# v1_0.net
KiCad netlist of a schematic drawn in Altium Designer
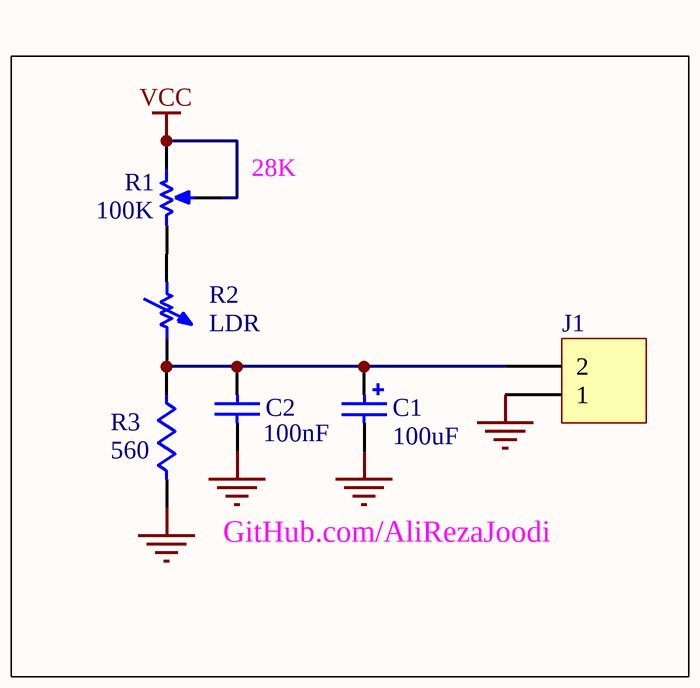
[diagram p0: v1.0.SchDoc]

(export (version "E")
  (design (tool "Eeschema 10.0.6"))
  (components
    (comp (ref "C1")
      (value "100uF")
      (footprint "CAPPR2.5-6.3x5")
      (description "Polarized Capacitor (Radial)")
      (fields
        (field (name "MANUFACTURER") "Generic Components")
        (field (name "Comment") "Cap Pol1")
        (field (name "PUBLISHER") "Altium Limited")
      )
      (libsource (lib "Miscellaneous Devices") (part "Cap Pol1"))
    )
    (comp (ref "C2")
      (value "100nF")
      (footprint "CAPNTO2.54-3.05x1.78A")
      (description "Capacitor")
      (fields
        (field (name "MANUFACTURER") "Generic Components")
        (field (name "Comment") "Cap")
        (field (name "PUBLISHER") "Altium Limited")
      )
      (libsource (lib "Miscellaneous Devices") (part "Cap"))
    )
    (comp (ref "J1")
      (value "Header")
      (footprint "Fonics_2PIN_1")
      (description "Header, 2-Pin")
      (fields (field (name "PUBLISHER") "Altium Limited"))
      (libsource (lib "Miscellaneous Connectors") (part "Header 2"))
    )
    (comp (ref "R1")
      (value "100K")
      (footprint "VR4_")
      (description "Potentiometer")
      (fields
        (field (name "MANUFACTURER") "Generic Components")
        (field (name "Comment") "R15")
        (field (name "PUBLISHER") "Altium Limited")
      )
      (libsource (lib "my Libraries") (part "RPot1"))
    )
    (comp (ref "R2")
      (value "LDR")
      (footprint "Fonics_2PIN_1")
      (description "Variable Resistor")
      (fields
        (field (name "MANUFACTURER") "Generic Components")
        (field (name "Comment") "Res Adj1")
        (field (name "PUBLISHER") "Altium Limited")
      )
      (libsource (lib "Miscellaneous Devices") (part "Res Adj1"))
    )
    (comp (ref "R3")
      (value "560")
      (footprint "AXIAL-0.4")
      (description "Resistor")
      (fields
        (field (name "MANUFACTURER") "Generic Components")
        (field (name "Comment") "Res1")
        (field (name "PUBLISHER") "Altium Limited")
      )
      (libsource (lib "Miscellaneous Devices") (part "Res1"))
    )
  )
  (nets
    (net (code "1") (name "GND") (class "Default")
      (node (ref "C1") (pin "2") (pinfunction "2_2") (pintype "passive"))
      (node (ref "C2") (pin "1") (pinfunction "1_1") (pintype "passive"))
      (node (ref "J1") (pin "1") (pinfunction "1_1") (pintype "passive"))
      (node (ref "R3") (pin "2") (pinfunction "2_2") (pintype "passive"))
    )
    (net (code "2") (name "Net-(C1-Pad1)") (class "Default")
      (node (ref "C1") (pin "1") (pinfunction "1_1") (pintype "passive"))
      (node (ref "C2") (pin "2") (pinfunction "2_2") (pintype "passive"))
      (node (ref "J1") (pin "2") (pinfunction "2_2") (pintype "passive"))
      (node (ref "R2") (pin "2") (pinfunction "2_2") (pintype "passive"))
      (node (ref "R3") (pin "1") (pinfunction "1_1") (pintype "passive"))
    )
    (net (code "3") (name "Net-(R1-BOT)") (class "Default")
      (node (ref "R1") (pin "2") (pinfunction "BOT_2") (pintype "passive"))
      (node (ref "R2") (pin "1") (pinfunction "1_1") (pintype "passive"))
    )
    (net (code "4") (name "VCC") (class "Default")
      (node (ref "R1") (pin "1") (pinfunction "TOP_1") (pintype "passive"))
      (node (ref "R1") (pin "3") (pinfunction "TAP_3") (pintype "passive"))
    )
  )
)
